# MCU.net
KiCad netlist of a schematic drawn in Altium Designer
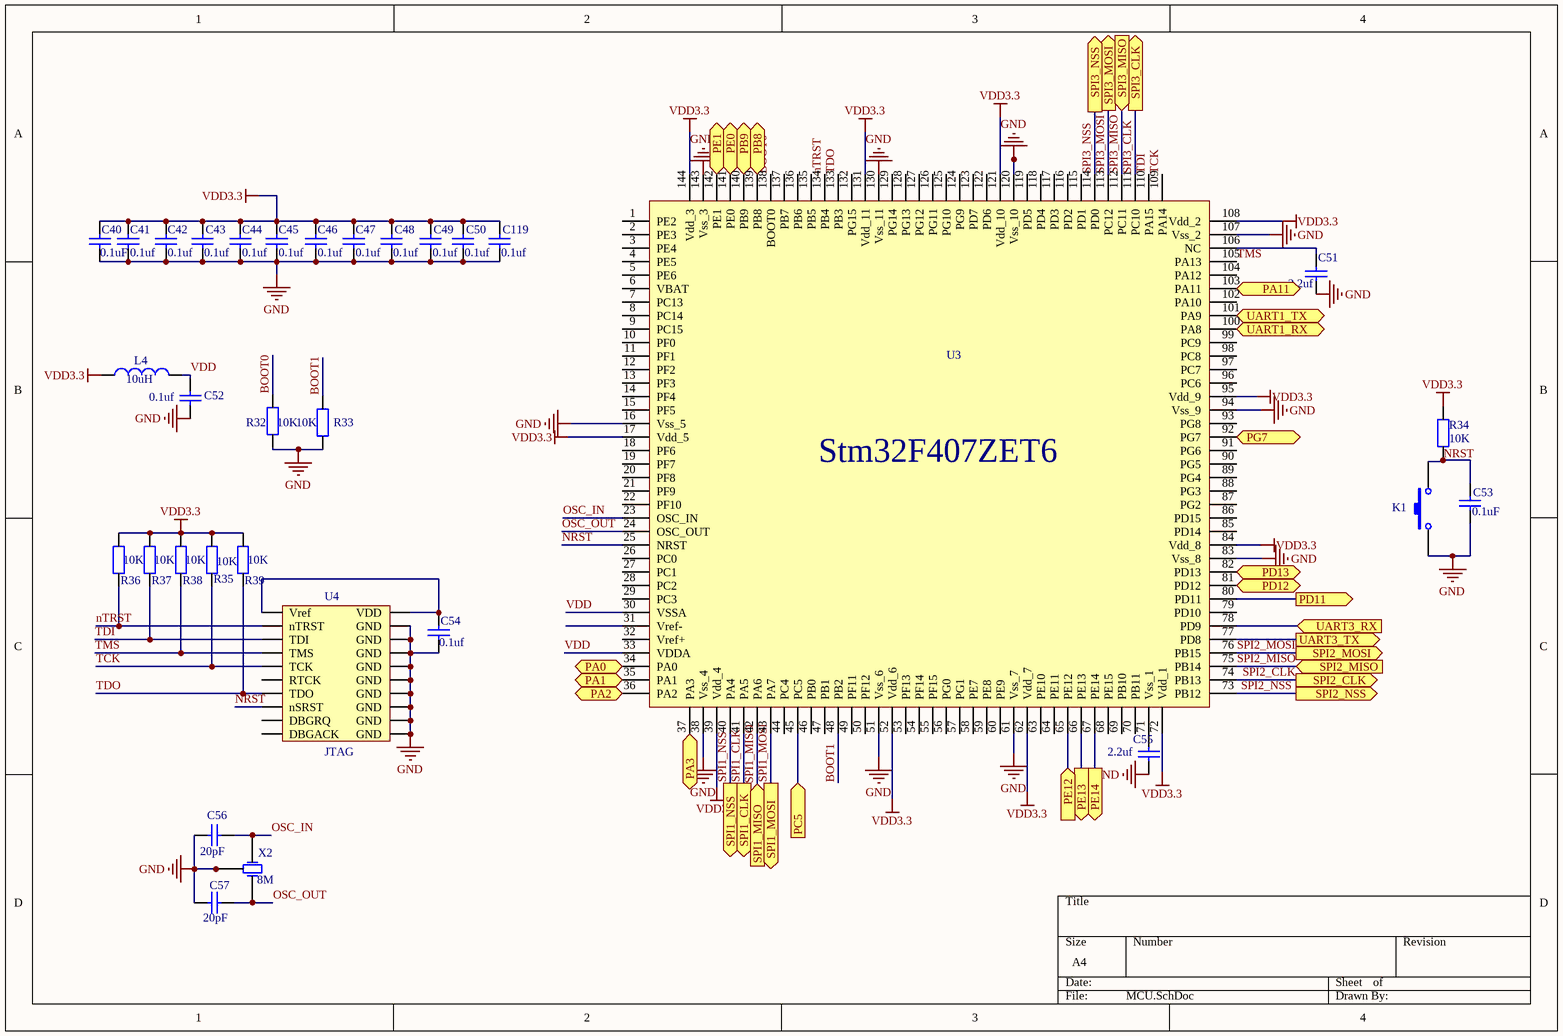
[diagram p0: MCU.SchDoc]

(export (version "E")
  (design (tool "Eeschema 10.0.6"))
  (components
    (comp (ref "C40")
      (value "0.1uF")
      (footprint "0603")
      (fields (field (name "Comment") "Capacitor-0805"))
      (libsource (lib "集成库—大岐") (part "Capacitor-0805"))
    )
    (comp (ref "C41")
      (value "0.1uf")
      (footprint "0603")
      (fields (field (name "Comment") "Capacitor-0805"))
      (libsource (lib "集成库—大岐") (part "Capacitor-0805"))
    )
    (comp (ref "C42")
      (value "0.1uf")
      (footprint "0603")
      (fields (field (name "Comment") "Capacitor-0805"))
      (libsource (lib "集成库—大岐") (part "Capacitor-0805"))
    )
    (comp (ref "C43")
      (value "0.1uf")
      (footprint "0603")
      (fields (field (name "Comment") "Capacitor-0805"))
      (libsource (lib "集成库—大岐") (part "Capacitor-0805"))
    )
    (comp (ref "C44")
      (value "0.1uf")
      (footprint "0603")
      (fields (field (name "Comment") "Capacitor-0805"))
      (libsource (lib "集成库—大岐") (part "Capacitor-0805"))
    )
    (comp (ref "C45")
      (value "0.1uf")
      (footprint "0603")
      (fields (field (name "Comment") "Capacitor-0805"))
      (libsource (lib "集成库—大岐") (part "Capacitor-0805"))
    )
    (comp (ref "C46")
      (value "0.1uf")
      (footprint "0603")
      (fields (field (name "Comment") "Capacitor-0805"))
      (libsource (lib "集成库—大岐") (part "Capacitor-0805"))
    )
    (comp (ref "C47")
      (value "0.1uf")
      (footprint "0603")
      (fields (field (name "Comment") "Capacitor-0805"))
      (libsource (lib "集成库—大岐") (part "Capacitor-0805"))
    )
    (comp (ref "C48")
      (value "0.1uf")
      (footprint "0603")
      (fields (field (name "Comment") "Capacitor-0805"))
      (libsource (lib "集成库—大岐") (part "Capacitor-0805"))
    )
    (comp (ref "C49")
      (value "0.1uf")
      (footprint "0603")
      (fields (field (name "Comment") "Capacitor-0805"))
      (libsource (lib "集成库—大岐") (part "Capacitor-0805"))
    )
    (comp (ref "C50")
      (value "0.1uf")
      (footprint "0603")
      (fields (field (name "Comment") "Capacitor-0805"))
      (libsource (lib "集成库—大岐") (part "Capacitor-0805"))
    )
    (comp (ref "C51")
      (value "2.2uf")
      (footprint "0603")
      (fields (field (name "Comment") "Capacitor-0603"))
      (libsource (lib "原理图库") (part "Capacitor-0603"))
    )
    (comp (ref "C52")
      (value "0.1uf")
      (footprint "0603")
      (fields (field (name "Comment") "Capacitor-0805"))
      (libsource (lib "集成库—大岐") (part "Capacitor-0805"))
    )
    (comp (ref "C53")
      (value "0.1uF")
      (footprint "0603")
      (fields (field (name "Comment") "Capacitor-0805"))
      (libsource (lib "原理图库") (part "Capacitor-0805"))
    )
    (comp (ref "C54")
      (value "0.1uf")
      (footprint "0603")
      (fields (field (name "Comment") "Capacitor-0805"))
      (libsource (lib "集成库—大岐") (part "Capacitor-0805"))
    )
    (comp (ref "C55")
      (value "2.2uf")
      (footprint "0603")
      (fields (field (name "Comment") "Capacitor-0603"))
      (libsource (lib "原理图库") (part "Capacitor-0603"))
    )
    (comp (ref "C56")
      (value "20pF")
      (footprint "0603")
      (fields (field (name "Comment") "Capacitor-0805"))
      (libsource (lib "原理图库") (part "Capacitor-0805"))
    )
    (comp (ref "C57")
      (value "20pF")
      (footprint "0603")
      (fields (field (name "Comment") "Capacitor-0805"))
      (libsource (lib "原理图库") (part "Capacitor-0805"))
    )
    (comp (ref "C119")
      (value "0.1uf")
      (footprint "0603")
      (fields (field (name "Comment") "Capacitor-0805"))
      (libsource (lib "集成库—大岐") (part "Capacitor-0805"))
    )
    (comp (ref "K1") (value "按键") (footprint "贴片按键") (libsource (lib "原理图库") (part "按键")))
    (comp (ref "L4")
      (value "10uH")
      (footprint "0805")
      (fields (field (name "Comment") "Inductor"))
      (libsource (lib "集成库—大岐") (part "Inductor"))
    )
    (comp (ref "R32")
      (value "10K")
      (footprint "0603")
      (fields (field (name "Comment") "Resistor-0805"))
      (libsource (lib "集成库—大岐") (part "Resistor-0805"))
    )
    (comp (ref "R33")
      (value "10K")
      (footprint "0603")
      (fields (field (name "Comment") "Resistor-0805"))
      (libsource (lib "集成库—大岐") (part "Resistor-0805"))
    )
    (comp (ref "R34")
      (value "10K")
      (footprint "0603")
      (fields (field (name "Comment") "Resistor-0805"))
      (libsource (lib "原理图库") (part "Resistor-0805"))
    )
    (comp (ref "R35")
      (value "10K")
      (footprint "0603")
      (fields (field (name "Comment") "Resistor-0805"))
      (libsource (lib "原理图库") (part "Resistor-0805"))
    )
    (comp (ref "R36")
      (value "10K")
      (footprint "0603")
      (fields (field (name "Comment") "Resistor-0805"))
      (libsource (lib "原理图库") (part "Resistor-0805"))
    )
    (comp (ref "R37")
      (value "10K")
      (footprint "0603")
      (fields (field (name "Comment") "Resistor-0805"))
      (libsource (lib "原理图库") (part "Resistor-0805"))
    )
    (comp (ref "R38")
      (value "10K")
      (footprint "0603")
      (fields (field (name "Comment") "Resistor-0805"))
      (libsource (lib "原理图库") (part "Resistor-0805"))
    )
    (comp (ref "R39")
      (value "10K")
      (footprint "0603")
      (fields (field (name "Comment") "Resistor-0805"))
      (libsource (lib "原理图库") (part "Resistor-0805"))
    )
    (comp (ref "U3")
      (value "STM32F407ZET6")
      (footprint "Stm32f407ZET6 - duplicate")
      (libsource (lib "原理图库") (part "STM32F407ZET6"))
    )
    (comp (ref "U4") (value "JTAG") (footprint "JTAG-20") (libsource (lib "原理图库") (part "JTAG")))
    (comp (ref "X2")
      (value "8M")
      (footprint "3225无源晶振")
      (fields (field (name "Comment") "3225无源晶振"))
      (libsource (lib "原理图库") (part "3225无源晶振"))
    )
  )
  (nets
    (net (code "1") (name "/BOOT0") (class "Default")
      (node (ref "R32") (pin "2") (pinfunction "2_2") (pintype "passive"))
      (node (ref "U3") (pin "138") (pinfunction "BOOT0_138") (pintype "passive"))
    )
    (net (code "2") (name "/BOOT1") (class "Default")
      (node (ref "R33") (pin "2") (pinfunction "2_2") (pintype "passive"))
      (node (ref "U3") (pin "48") (pinfunction "PB2_48") (pintype "passive"))
    )
    (net (code "3") (name "/NRST") (class "Default")
      (node (ref "C53") (pin "2") (pinfunction "2_2") (pintype "passive"))
      (node (ref "K1") (pin "2") (pinfunction "2_2") (pintype "passive"))
      (node (ref "R34") (pin "1") (pinfunction "1_1") (pintype "passive"))
      (node (ref "U3") (pin "25") (pinfunction "NRST_25") (pintype "passive"))
      (node (ref "U4") (pin "15") (pinfunction "nSRST_15") (pintype "passive"))
    )
    (net (code "4") (name "/OSC_IN") (class "Default")
      (node (ref "C56") (pin "2") (pinfunction "2_2") (pintype "passive"))
      (node (ref "U3") (pin "23") (pinfunction "OSC_IN_23") (pintype "passive"))
      (node (ref "X2") (pin "1") (pinfunction "OSC1_1") (pintype "passive"))
    )
    (net (code "5") (name "/OSC_OUT") (class "Default")
      (node (ref "C57") (pin "2") (pinfunction "2_2") (pintype "passive"))
      (node (ref "U3") (pin "24") (pinfunction "OSC_OUT_24") (pintype "passive"))
      (node (ref "X2") (pin "3") (pinfunction "OSC2_3") (pintype "passive"))
    )
    (net (code "6") (name "/PA0") (class "Default")
      (node (ref "U3") (pin "34") (pinfunction "PA0_34") (pintype "passive"))
    )
    (net (code "7") (name "/PA1") (class "Default")
      (node (ref "U3") (pin "35") (pinfunction "PA1_35") (pintype "passive"))
    )
    (net (code "8") (name "/PA2") (class "Default")
      (node (ref "U3") (pin "36") (pinfunction "PA2_36") (pintype "passive"))
    )
    (net (code "9") (name "/PA3") (class "Default")
      (node (ref "U3") (pin "37") (pinfunction "PA3_37") (pintype "passive"))
    )
    (net (code "10") (name "/PA11") (class "Default")
      (node (ref "U3") (pin "103") (pinfunction "PA11_103") (pintype "passive"))
    )
    (net (code "11") (name "/PB8") (class "Default")
      (node (ref "U3") (pin "139") (pinfunction "PB8_139") (pintype "passive"))
    )
    (net (code "12") (name "/PB9") (class "Default")
      (node (ref "U3") (pin "140") (pinfunction "PB9_140") (pintype "passive"))
    )
    (net (code "13") (name "/PC5") (class "Default")
      (node (ref "U3") (pin "45") (pinfunction "PC5_45") (pintype "passive"))
    )
    (net (code "14") (name "/PD11") (class "Default")
      (node (ref "U3") (pin "80") (pinfunction "PD11_80") (pintype "passive"))
    )
    (net (code "15") (name "/PD12") (class "Default")
      (node (ref "U3") (pin "81") (pinfunction "PD12_81") (pintype "passive"))
    )
    (net (code "16") (name "/PD13") (class "Default")
      (node (ref "U3") (pin "82") (pinfunction "PD13_82") (pintype "passive"))
    )
    (net (code "17") (name "/PE0") (class "Default")
      (node (ref "U3") (pin "141") (pinfunction "PE0_141") (pintype "passive"))
    )
    (net (code "18") (name "/PE1") (class "Default")
      (node (ref "U3") (pin "142") (pinfunction "PE1_142") (pintype "passive"))
    )
    (net (code "19") (name "/PE12") (class "Default")
      (node (ref "U3") (pin "65") (pinfunction "PE12_65") (pintype "passive"))
    )
    (net (code "20") (name "/PE13") (class "Default")
      (node (ref "U3") (pin "66") (pinfunction "PE13_66") (pintype "passive"))
    )
    (net (code "21") (name "/PE14") (class "Default")
      (node (ref "U3") (pin "67") (pinfunction "PE14_67") (pintype "passive"))
    )
    (net (code "22") (name "/PG7") (class "Default")
      (node (ref "U3") (pin "92") (pinfunction "PG7_92") (pintype "passive"))
    )
    (net (code "23") (name "/SPI1_CLK") (class "Default")
      (node (ref "U3") (pin "41") (pinfunction "PA5_41") (pintype "passive"))
    )
    (net (code "24") (name "/SPI1_MISO") (class "Default")
      (node (ref "U3") (pin "42") (pinfunction "PA6_42") (pintype "passive"))
    )
    (net (code "25") (name "/SPI1_MOSI") (class "Default")
      (node (ref "U3") (pin "43") (pinfunction "PA7_43") (pintype "passive"))
    )
    (net (code "26") (name "/SPI1_NSS") (class "Default")
      (node (ref "U3") (pin "40") (pinfunction "PA4_40") (pintype "passive"))
    )
    (net (code "27") (name "/SPI2_CLK") (class "Default")
      (node (ref "U3") (pin "74") (pinfunction "PB13_74") (pintype "passive"))
    )
    (net (code "28") (name "/SPI2_MISO") (class "Default")
      (node (ref "U3") (pin "75") (pinfunction "PB14_75") (pintype "passive"))
    )
    (net (code "29") (name "/SPI2_MOSI") (class "Default")
      (node (ref "U3") (pin "76") (pinfunction "PB15_76") (pintype "passive"))
    )
    (net (code "30") (name "/SPI2_NSS") (class "Default")
      (node (ref "U3") (pin "73") (pinfunction "PB12_73") (pintype "passive"))
    )
    (net (code "31") (name "/SPI3_CLK") (class "Default")
      (node (ref "U3") (pin "111") (pinfunction "PC10_111") (pintype "passive"))
    )
    (net (code "32") (name "/SPI3_MISO") (class "Default")
      (node (ref "U3") (pin "112") (pinfunction "PC11_112") (pintype "passive"))
    )
    (net (code "33") (name "/SPI3_MOSI") (class "Default")
      (node (ref "U3") (pin "113") (pinfunction "PC12_113") (pintype "passive"))
    )
    (net (code "34") (name "/SPI3_NSS") (class "Default")
      (node (ref "U3") (pin "114") (pinfunction "PD0_114") (pintype "passive"))
    )
    (net (code "35") (name "/TCK") (class "Default")
      (node (ref "R35") (pin "1") (pinfunction "1_1") (pintype "passive"))
      (node (ref "U3") (pin "109") (pinfunction "PA14_109") (pintype "passive"))
      (node (ref "U4") (pin "9") (pinfunction "TCK_9") (pintype "passive"))
    )
    (net (code "36") (name "/TDI") (class "Default")
      (node (ref "R37") (pin "1") (pinfunction "1_1") (pintype "passive"))
      (node (ref "U3") (pin "110") (pinfunction "PA15_110") (pintype "passive"))
      (node (ref "U4") (pin "5") (pinfunction "TDI_5") (pintype "passive"))
    )
    (net (code "37") (name "/TDO") (class "Default")
      (node (ref "R39") (pin "1") (pinfunction "1_1") (pintype "passive"))
      (node (ref "U3") (pin "133") (pinfunction "PB3_133") (pintype "passive"))
      (node (ref "U4") (pin "13") (pinfunction "TDO_13") (pintype "passive"))
    )
    (net (code "38") (name "/TMS") (class "Default")
      (node (ref "R38") (pin "1") (pinfunction "1_1") (pintype "passive"))
      (node (ref "U3") (pin "105") (pinfunction "PA13_105") (pintype "passive"))
      (node (ref "U4") (pin "7") (pinfunction "TMS_7") (pintype "passive"))
    )
    (net (code "39") (name "/UART1_RX") (class "Default")
      (node (ref "U3") (pin "100") (pinfunction "PA8_100") (pintype "passive"))
    )
    (net (code "40") (name "/UART1_TX") (class "Default")
      (node (ref "U3") (pin "101") (pinfunction "PA9_101") (pintype "passive"))
    )
    (net (code "41") (name "/UART3_RX") (class "Default")
      (node (ref "U3") (pin "78") (pinfunction "PD9_78") (pintype "passive"))
    )
    (net (code "42") (name "/UART3_TX") (class "Default")
      (node (ref "U3") (pin "77") (pinfunction "PD8_77") (pintype "passive"))
    )
    (net (code "43") (name "/VDD") (class "Default")
      (node (ref "C52") (pin "2") (pinfunction "2_2") (pintype "passive"))
      (node (ref "L4") (pin "2") (pinfunction "2_2") (pintype "passive"))
      (node (ref "U3") (pin "30") (pinfunction "VSSA_30") (pintype "passive"))
      (node (ref "U3") (pin "33") (pinfunction "VDDA_33") (pintype "passive"))
    )
    (net (code "44") (name "/nTRST") (class "Default")
      (node (ref "R36") (pin "1") (pinfunction "1_1") (pintype "passive"))
      (node (ref "U3") (pin "134") (pinfunction "PB4_134") (pintype "passive"))
      (node (ref "U4") (pin "3") (pinfunction "nTRST_3") (pintype "passive"))
    )
    (net (code "45") (name "GND") (class "Default")
      (node (ref "C119") (pin "1") (pinfunction "1_1") (pintype "passive"))
      (node (ref "C40") (pin "1") (pinfunction "1_1") (pintype "passive"))
      (node (ref "C41") (pin "1") (pinfunction "1_1") (pintype "passive"))
      (node (ref "C42") (pin "1") (pinfunction "1_1") (pintype "passive"))
      (node (ref "C43") (pin "1") (pinfunction "1_1") (pintype "passive"))
      (node (ref "C44") (pin "1") (pinfunction "1_1") (pintype "passive"))
      (node (ref "C45") (pin "1") (pinfunction "1_1") (pintype "passive"))
      (node (ref "C46") (pin "1") (pinfunction "1_1") (pintype "passive"))
      (node (ref "C47") (pin "1") (pinfunction "1_1") (pintype "passive"))
      (node (ref "C48") (pin "1") (pinfunction "1_1") (pintype "passive"))
      (node (ref "C49") (pin "1") (pinfunction "1_1") (pintype "passive"))
      (node (ref "C50") (pin "1") (pinfunction "1_1") (pintype "passive"))
      (node (ref "C51") (pin "1") (pinfunction "1_1") (pintype "passive"))
      (node (ref "C52") (pin "1") (pinfunction "1_1") (pintype "passive"))
      (node (ref "C53") (pin "1") (pinfunction "1_1") (pintype "passive"))
      (node (ref "C54") (pin "1") (pinfunction "1_1") (pintype "passive"))
      (node (ref "C55") (pin "1") (pinfunction "1_1") (pintype "passive"))
      (node (ref "C56") (pin "1") (pinfunction "1_1") (pintype "passive"))
      (node (ref "C57") (pin "1") (pinfunction "1_1") (pintype "passive"))
      (node (ref "K1") (pin "1") (pinfunction "1_1") (pintype "passive"))
      (node (ref "R32") (pin "1") (pinfunction "1_1") (pintype "passive"))
      (node (ref "R33") (pin "1") (pinfunction "1_1") (pintype "passive"))
      (node (ref "U3") (pin "107") (pinfunction "Vss_2_107") (pintype "passive"))
      (node (ref "U3") (pin "120") (pinfunction "Vss_10_120") (pintype "passive"))
      (node (ref "U3") (pin "130") (pinfunction "Vss_11_130") (pintype "passive"))
      (node (ref "U3") (pin "143") (pinfunction "Vss_3_143") (pintype "passive"))
      (node (ref "U3") (pin "16") (pinfunction "Vss_5_16") (pintype "passive"))
      (node (ref "U3") (pin "38") (pinfunction "Vss_4_38") (pintype "passive"))
      (node (ref "U3") (pin "51") (pinfunction "Vss_6_51") (pintype "passive"))
      (node (ref "U3") (pin "61") (pinfunction "Vss_7_61") (pintype "passive"))
      (node (ref "U3") (pin "83") (pinfunction "Vss_8_83") (pintype "passive"))
      (node (ref "U3") (pin "94") (pinfunction "Vss_9_94") (pintype "passive"))
      (node (ref "U4") (pin "10") (pinfunction "GND_10") (pintype "passive"))
      (node (ref "U4") (pin "12") (pinfunction "GND_12") (pintype "passive"))
      (node (ref "U4") (pin "14") (pinfunction "GND_14") (pintype "passive"))
      (node (ref "U4") (pin "16") (pinfunction "GND_16") (pintype "passive"))
      (node (ref "U4") (pin "18") (pinfunction "GND_18") (pintype "passive"))
      (node (ref "U4") (pin "20") (pinfunction "GND_20") (pintype "passive"))
      (node (ref "U4") (pin "4") (pinfunction "GND_4") (pintype "passive"))
      (node (ref "U4") (pin "6") (pinfunction "GND_6") (pintype "passive"))
      (node (ref "U4") (pin "8") (pinfunction "GND_8") (pintype "passive"))
      (node (ref "X2") (pin "2") (pinfunction "GND_2") (pintype "passive"))
      (node (ref "X2") (pin "4") (pinfunction "GND_4") (pintype "passive"))
    )
    (net (code "46") (name "Net-(U3-NC)") (class "Default")
      (node (ref "C51") (pin "2") (pinfunction "2_2") (pintype "passive"))
      (node (ref "U3") (pin "106") (pinfunction "NC_106") (pintype "passive"))
    )
    (net (code "47") (name "Net-(U3-Vss_1)") (class "Default")
      (node (ref "C55") (pin "2") (pinfunction "2_2") (pintype "passive"))
      (node (ref "U3") (pin "71") (pinfunction "Vss_1_71") (pintype "passive"))
    )
    (net (code "48") (name "Net-(U4-VDD)") (class "Default")
      (node (ref "C54") (pin "2") (pinfunction "2_2") (pintype "passive"))
      (node (ref "U4") (pin "1") (pinfunction "Vref_1") (pintype "passive"))
      (node (ref "U4") (pin "2") (pinfunction "VDD_2") (pintype "passive"))
    )
    (net (code "49") (name "VDD3.3") (class "Default")
      (node (ref "C119") (pin "2") (pinfunction "2_2") (pintype "passive"))
      (node (ref "C40") (pin "2") (pinfunction "2_2") (pintype "passive"))
      (node (ref "C41") (pin "2") (pinfunction "2_2") (pintype "passive"))
      (node (ref "C42") (pin "2") (pinfunction "2_2") (pintype "passive"))
      (node (ref "C43") (pin "2") (pinfunction "2_2") (pintype "passive"))
      (node (ref "C44") (pin "2") (pinfunction "2_2") (pintype "passive"))
      (node (ref "C45") (pin "2") (pinfunction "2_2") (pintype "passive"))
      (node (ref "C46") (pin "2") (pinfunction "2_2") (pintype "passive"))
      (node (ref "C47") (pin "2") (pinfunction "2_2") (pintype "passive"))
      (node (ref "C48") (pin "2") (pinfunction "2_2") (pintype "passive"))
      (node (ref "C49") (pin "2") (pinfunction "2_2") (pintype "passive"))
      (node (ref "C50") (pin "2") (pinfunction "2_2") (pintype "passive"))
      (node (ref "L4") (pin "1") (pinfunction "1_1") (pintype "passive"))
      (node (ref "R34") (pin "2") (pinfunction "2_2") (pintype "passive"))
      (node (ref "R35") (pin "2") (pinfunction "2_2") (pintype "passive"))
      (node (ref "R36") (pin "2") (pinfunction "2_2") (pintype "passive"))
      (node (ref "R37") (pin "2") (pinfunction "2_2") (pintype "passive"))
      (node (ref "R38") (pin "2") (pinfunction "2_2") (pintype "passive"))
      (node (ref "R39") (pin "2") (pinfunction "2_2") (pintype "passive"))
      (node (ref "U3") (pin "108") (pinfunction "Vdd_2_108") (pintype "passive"))
      (node (ref "U3") (pin "121") (pinfunction "Vdd_10_121") (pintype "passive"))
      (node (ref "U3") (pin "131") (pinfunction "Vdd_11_131") (pintype "passive"))
      (node (ref "U3") (pin "144") (pinfunction "Vdd_3_144") (pintype "passive"))
      (node (ref "U3") (pin "17") (pinfunction "Vdd_5_17") (pintype "passive"))
      (node (ref "U3") (pin "39") (pinfunction "Vdd_4_39") (pintype "passive"))
      (node (ref "U3") (pin "52") (pinfunction "Vdd_6_52") (pintype "passive"))
      (node (ref "U3") (pin "62") (pinfunction "Vdd_7_62") (pintype "passive"))
      (node (ref "U3") (pin "72") (pinfunction "Vdd_1_72") (pintype "passive"))
      (node (ref "U3") (pin "84") (pinfunction "Vdd_8_84") (pintype "passive"))
      (node (ref "U3") (pin "95") (pinfunction "Vdd_9_95") (pintype "passive"))
    )
    (net (code "50") (name "unconnected-(U3-PA10-Pad102)") (class "Default")
      (node (ref "U3") (pin "102") (pinfunction "PA10_102") (pintype "passive"))
    )
    (net (code "51") (name "unconnected-(U3-PA12-Pad104)") (class "Default")
      (node (ref "U3") (pin "104") (pinfunction "PA12_104") (pintype "passive"))
    )
    (net (code "52") (name "unconnected-(U3-PB0-Pad46)") (class "Default")
      (node (ref "U3") (pin "46") (pinfunction "PB0_46") (pintype "passive"))
    )
    (net (code "53") (name "unconnected-(U3-PB1-Pad47)") (class "Default")
      (node (ref "U3") (pin "47") (pinfunction "PB1_47") (pintype "passive"))
    )
    (net (code "54") (name "unconnected-(U3-PB5-Pad135)") (class "Default")
      (node (ref "U3") (pin "135") (pinfunction "PB5_135") (pintype "passive"))
    )
    (net (code "55") (name "unconnected-(U3-PB6-Pad136)") (class "Default")
      (node (ref "U3") (pin "136") (pinfunction "PB6_136") (pintype "passive"))
    )
    (net (code "56") (name "unconnected-(U3-PB7-Pad137)") (class "Default")
      (node (ref "U3") (pin "137") (pinfunction "PB7_137") (pintype "passive"))
    )
    (net (code "57") (name "unconnected-(U3-PB10-Pad69)") (class "Default")
      (node (ref "U3") (pin "69") (pinfunction "PB10_69") (pintype "passive"))
    )
    (net (code "58") (name "unconnected-(U3-PB11-Pad70)") (class "Default")
      (node (ref "U3") (pin "70") (pinfunction "PB11_70") (pintype "passive"))
    )
    (net (code "59") (name "unconnected-(U3-PC0-Pad26)") (class "Default")
      (node (ref "U3") (pin "26") (pinfunction "PC0_26") (pintype "passive"))
    )
    (net (code "60") (name "unconnected-(U3-PC1-Pad27)") (class "Default")
      (node (ref "U3") (pin "27") (pinfunction "PC1_27") (pintype "passive"))
    )
    (net (code "61") (name "unconnected-(U3-PC2-Pad28)") (class "Default")
      (node (ref "U3") (pin "28") (pinfunction "PC2_28") (pintype "passive"))
    )
    (net (code "62") (name "unconnected-(U3-PC3-Pad29)") (class "Default")
      (node (ref "U3") (pin "29") (pinfunction "PC3_29") (pintype "passive"))
    )
    (net (code "63") (name "unconnected-(U3-PC4-Pad44)") (class "Default")
      (node (ref "U3") (pin "44") (pinfunction "PC4_44") (pintype "passive"))
    )
    (net (code "64") (name "unconnected-(U3-PC6-Pad96)") (class "Default")
      (node (ref "U3") (pin "96") (pinfunction "PC6_96") (pintype "passive"))
    )
    (net (code "65") (name "unconnected-(U3-PC7-Pad97)") (class "Default")
      (node (ref "U3") (pin "97") (pinfunction "PC7_97") (pintype "passive"))
    )
    (net (code "66") (name "unconnected-(U3-PC8-Pad98)") (class "Default")
      (node (ref "U3") (pin "98") (pinfunction "PC8_98") (pintype "passive"))
    )
    (net (code "67") (name "unconnected-(U3-PC9-Pad99)") (class "Default")
      (node (ref "U3") (pin "99") (pinfunction "PC9_99") (pintype "passive"))
    )
    (net (code "68") (name "unconnected-(U3-PC13-Pad7)") (class "Default")
      (node (ref "U3") (pin "7") (pinfunction "PC13_7") (pintype "passive"))
    )
    (net (code "69") (name "unconnected-(U3-PC14-Pad8)") (class "Default")
      (node (ref "U3") (pin "8") (pinfunction "PC14_8") (pintype "passive"))
    )
    (net (code "70") (name "unconnected-(U3-PC15-Pad9)") (class "Default")
      (node (ref "U3") (pin "9") (pinfunction "PC15_9") (pintype "passive"))
    )
    (net (code "71") (name "unconnected-(U3-PD1-Pad115)") (class "Default")
      (node (ref "U3") (pin "115") (pinfunction "PD1_115") (pintype "passive"))
    )
    (net (code "72") (name "unconnected-(U3-PD2-Pad116)") (class "Default")
      (node (ref "U3") (pin "116") (pinfunction "PD2_116") (pintype "passive"))
    )
    (net (code "73") (name "unconnected-(U3-PD3-Pad117)") (class "Default")
      (node (ref "U3") (pin "117") (pinfunction "PD3_117") (pintype "passive"))
    )
    (net (code "74") (name "unconnected-(U3-PD4-Pad118)") (class "Default")
      (node (ref "U3") (pin "118") (pinfunction "PD4_118") (pintype "passive"))
    )
    (net (code "75") (name "unconnected-(U3-PD5-Pad119)") (class "Default")
      (node (ref "U3") (pin "119") (pinfunction "PD5_119") (pintype "passive"))
    )
    (net (code "76") (name "unconnected-(U3-PD6-Pad122)") (class "Default")
      (node (ref "U3") (pin "122") (pinfunction "PD6_122") (pintype "passive"))
    )
    (net (code "77") (name "unconnected-(U3-PD7-Pad123)") (class "Default")
      (node (ref "U3") (pin "123") (pinfunction "PD7_123") (pintype "passive"))
    )
    (net (code "78") (name "unconnected-(U3-PD10-Pad79)") (class "Default")
      (node (ref "U3") (pin "79") (pinfunction "PD10_79") (pintype "passive"))
    )
    (net (code "79") (name "unconnected-(U3-PD14-Pad85)") (class "Default")
      (node (ref "U3") (pin "85") (pinfunction "PD14_85") (pintype "passive"))
    )
    (net (code "80") (name "unconnected-(U3-PD15-Pad86)") (class "Default")
      (node (ref "U3") (pin "86") (pinfunction "PD15_86") (pintype "passive"))
    )
    (net (code "81") (name "unconnected-(U3-PE2-Pad1)") (class "Default")
      (node (ref "U3") (pin "1") (pinfunction "PE2_1") (pintype "passive"))
    )
    (net (code "82") (name "unconnected-(U3-PE3-Pad2)") (class "Default")
      (node (ref "U3") (pin "2") (pinfunction "PE3_2") (pintype "passive"))
    )
    (net (code "83") (name "unconnected-(U3-PE4-Pad3)") (class "Default")
      (node (ref "U3") (pin "3") (pinfunction "PE4_3") (pintype "passive"))
    )
    (net (code "84") (name "unconnected-(U3-PE5-Pad4)") (class "Default")
      (node (ref "U3") (pin "4") (pinfunction "PE5_4") (pintype "passive"))
    )
    (net (code "85") (name "unconnected-(U3-PE6-Pad5)") (class "Default")
      (node (ref "U3") (pin "5") (pinfunction "PE6_5") (pintype "passive"))
    )
    (net (code "86") (name "unconnected-(U3-PE7-Pad58)") (class "Default")
      (node (ref "U3") (pin "58") (pinfunction "PE7_58") (pintype "passive"))
    )
    (net (code "87") (name "unconnected-(U3-PE8-Pad59)") (class "Default")
      (node (ref "U3") (pin "59") (pinfunction "PE8_59") (pintype "passive"))
    )
    (net (code "88") (name "unconnected-(U3-PE9-Pad60)") (class "Default")
      (node (ref "U3") (pin "60") (pinfunction "PE9_60") (pintype "passive"))
    )
    (net (code "89") (name "unconnected-(U3-PE10-Pad63)") (class "Default")
      (node (ref "U3") (pin "63") (pinfunction "PE10_63") (pintype "passive"))
    )
    (net (code "90") (name "unconnected-(U3-PE11-Pad64)") (class "Default")
      (node (ref "U3") (pin "64") (pinfunction "PE11_64") (pintype "passive"))
    )
    (net (code "91") (name "unconnected-(U3-PE15-Pad68)") (class "Default")
      (node (ref "U3") (pin "68") (pinfunction "PE15_68") (pintype "passive"))
    )
    (net (code "92") (name "unconnected-(U3-PF0-Pad10)") (class "Default")
      (node (ref "U3") (pin "10") (pinfunction "PF0_10") (pintype "passive"))
    )
    (net (code "93") (name "unconnected-(U3-PF1-Pad11)") (class "Default")
      (node (ref "U3") (pin "11") (pinfunction "PF1_11") (pintype "passive"))
    )
    (net (code "94") (name "unconnected-(U3-PF2-Pad12)") (class "Default")
      (node (ref "U3") (pin "12") (pinfunction "PF2_12") (pintype "passive"))
    )
    (net (code "95") (name "unconnected-(U3-PF3-Pad13)") (class "Default")
      (node (ref "U3") (pin "13") (pinfunction "PF3_13") (pintype "passive"))
    )
    (net (code "96") (name "unconnected-(U3-PF4-Pad14)") (class "Default")
      (node (ref "U3") (pin "14") (pinfunction "PF4_14") (pintype "passive"))
    )
    (net (code "97") (name "unconnected-(U3-PF5-Pad15)") (class "Default")
      (node (ref "U3") (pin "15") (pinfunction "PF5_15") (pintype "passive"))
    )
    (net (code "98") (name "unconnected-(U3-PF6-Pad18)") (class "Default")
      (node (ref "U3") (pin "18") (pinfunction "PF6_18") (pintype "passive"))
    )
    (net (code "99") (name "unconnected-(U3-PF7-Pad19)") (class "Default")
      (node (ref "U3") (pin "19") (pinfunction "PF7_19") (pintype "passive"))
    )
    (net (code "100") (name "unconnected-(U3-PF8-Pad20)") (class "Default")
      (node (ref "U3") (pin "20") (pinfunction "PF8_20") (pintype "passive"))
    )
    (net (code "101") (name "unconnected-(U3-PF9-Pad21)") (class "Default")
      (node (ref "U3") (pin "21") (pinfunction "PF9_21") (pintype "passive"))
    )
    (net (code "102") (name "unconnected-(U3-PF10-Pad22)") (class "Default")
      (node (ref "U3") (pin "22") (pinfunction "PF10_22") (pintype "passive"))
    )
    (net (code "103") (name "unconnected-(U3-PF11-Pad49)") (class "Default")
      (node (ref "U3") (pin "49") (pinfunction "PF11_49") (pintype "passive"))
    )
    (net (code "104") (name "unconnected-(U3-PF12-Pad50)") (class "Default")
      (node (ref "U3") (pin "50") (pinfunction "PF12_50") (pintype "passive"))
    )
    (net (code "105") (name "unconnected-(U3-PF13-Pad53)") (class "Default")
      (node (ref "U3") (pin "53") (pinfunction "PF13_53") (pintype "passive"))
    )
    (net (code "106") (name "unconnected-(U3-PF14-Pad54)") (class "Default")
      (node (ref "U3") (pin "54") (pinfunction "PF14_54") (pintype "passive"))
    )
    (net (code "107") (name "unconnected-(U3-PF15-Pad55)") (class "Default")
      (node (ref "U3") (pin "55") (pinfunction "PF15_55") (pintype "passive"))
    )
    (net (code "108") (name "unconnected-(U3-PG0-Pad56)") (class "Default")
      (node (ref "U3") (pin "56") (pinfunction "PG0_56") (pintype "passive"))
    )
    (net (code "109") (name "unconnected-(U3-PG1-Pad57)") (class "Default")
      (node (ref "U3") (pin "57") (pinfunction "PG1_57") (pintype "passive"))
    )
    (net (code "110") (name "unconnected-(U3-PG2-Pad87)") (class "Default")
      (node (ref "U3") (pin "87") (pinfunction "PG2_87") (pintype "passive"))
    )
    (net (code "111") (name "unconnected-(U3-PG3-Pad88)") (class "Default")
      (node (ref "U3") (pin "88") (pinfunction "PG3_88") (pintype "passive"))
    )
    (net (code "112") (name "unconnected-(U3-PG4-Pad89)") (class "Default")
      (node (ref "U3") (pin "89") (pinfunction "PG4_89") (pintype "passive"))
    )
    (net (code "113") (name "unconnected-(U3-PG5-Pad90)") (class "Default")
      (node (ref "U3") (pin "90") (pinfunction "PG5_90") (pintype "passive"))
    )
    (net (code "114") (name "unconnected-(U3-PG6-Pad91)") (class "Default")
      (node (ref "U3") (pin "91") (pinfunction "PG6_91") (pintype "passive"))
    )
    (net (code "115") (name "unconnected-(U3-PG8-Pad93)") (class "Default")
      (node (ref "U3") (pin "93") (pinfunction "PG8_93") (pintype "passive"))
    )
    (net (code "116") (name "unconnected-(U3-PG9-Pad124)") (class "Default")
      (node (ref "U3") (pin "124") (pinfunction "PG9_124") (pintype "passive"))
    )
    (net (code "117") (name "unconnected-(U3-PG10-Pad125)") (class "Default")
      (node (ref "U3") (pin "125") (pinfunction "PG10_125") (pintype "passive"))
    )
    (net (code "118") (name "unconnected-(U3-PG11-Pad126)") (class "Default")
      (node (ref "U3") (pin "126") (pinfunction "PG11_126") (pintype "passive"))
    )
    (net (code "119") (name "unconnected-(U3-PG12-Pad127)") (class "Default")
      (node (ref "U3") (pin "127") (pinfunction "PG12_127") (pintype "passive"))
    )
    (net (code "120") (name "unconnected-(U3-PG13-Pad128)") (class "Default")
      (node (ref "U3") (pin "128") (pinfunction "PG13_128") (pintype "passive"))
    )
    (net (code "121") (name "unconnected-(U3-PG14-Pad129)") (class "Default")
      (node (ref "U3") (pin "129") (pinfunction "PG14_129") (pintype "passive"))
    )
    (net (code "122") (name "unconnected-(U3-PG15-Pad132)") (class "Default")
      (node (ref "U3") (pin "132") (pinfunction "PG15_132") (pintype "passive"))
    )
    (net (code "123") (name "unconnected-(U3-VBAT-Pad6)") (class "Default")
      (node (ref "U3") (pin "6") (pinfunction "VBAT_6") (pintype "passive"))
    )
    (net (code "124") (name "unconnected-(U3-Vref+-Pad32)") (class "Default")
      (node (ref "U3") (pin "32") (pinfunction "Vref+_32") (pintype "passive"))
    )
    (net (code "125") (name "unconnected-(U3-Vref--Pad31)") (class "Default")
      (node (ref "U3") (pin "31") (pinfunction "Vref-_31") (pintype "passive"))
    )
    (net (code "126") (name "unconnected-(U4-DBGACK-Pad19)") (class "Default")
      (node (ref "U4") (pin "19") (pinfunction "DBGACK_19") (pintype "passive"))
    )
    (net (code "127") (name "unconnected-(U4-DBGRQ-Pad17)") (class "Default")
      (node (ref "U4") (pin "17") (pinfunction "DBGRQ_17") (pintype "passive"))
    )
    (net (code "128") (name "unconnected-(U4-RTCK-Pad11)") (class "Default")
      (node (ref "U4") (pin "11") (pinfunction "RTCK_11") (pintype "passive"))
    )
  )
)
